# ar_env.net
KiCad netlist of a schematic drawn in EAGLE
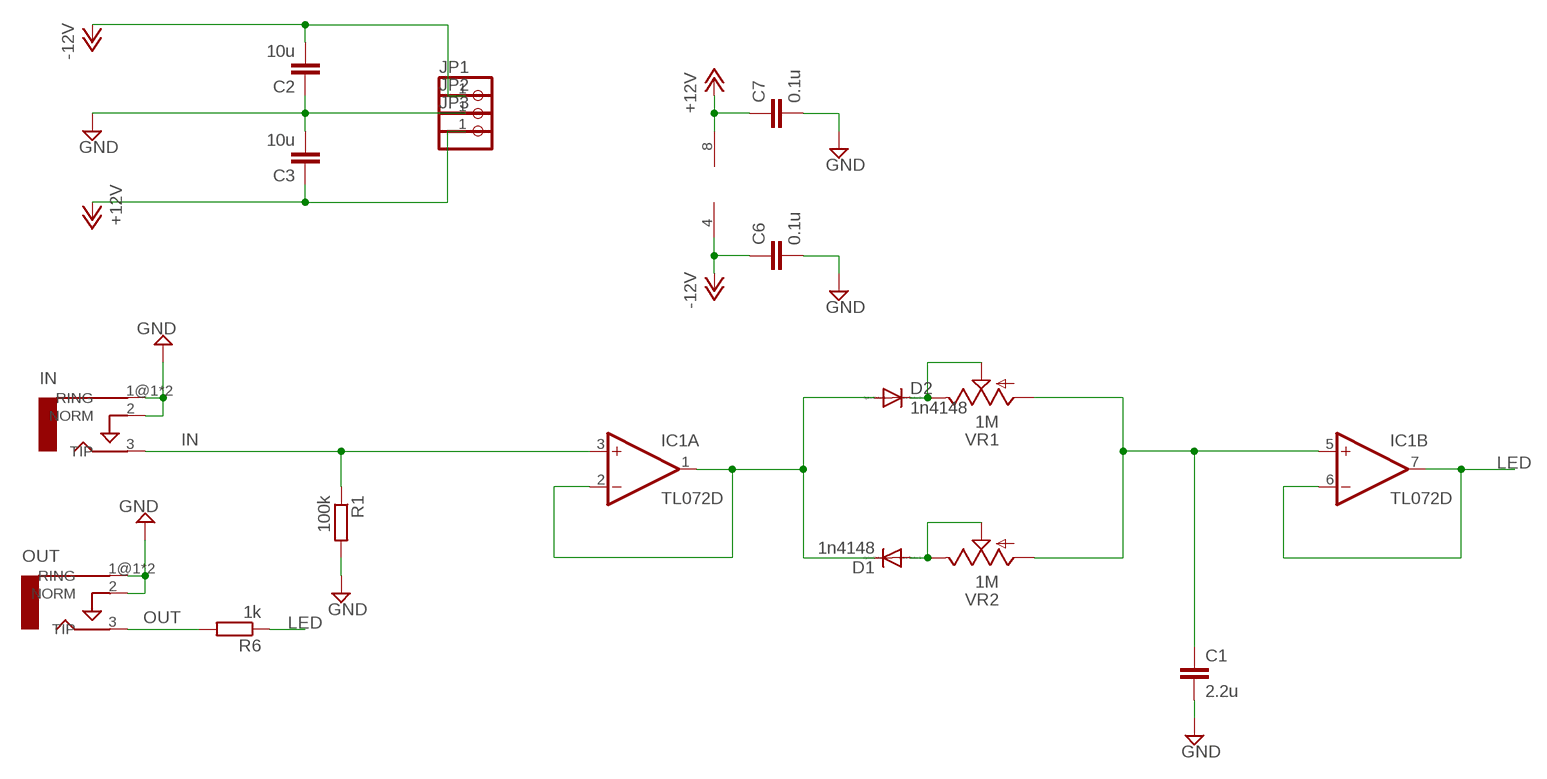
[diagram p0: schematic, sheet 1]

(export (version "E")
  (design (tool "Eeschema 10.0.6"))
  (components
    (comp (ref "C1")
      (value "2.2u")
      (footprint "eagle-import:C0805")
      (libsource (lib "eagle-import") (part "C-EUC0805"))
    )
    (comp (ref "C2")
      (value "10u")
      (footprint "eagle-import:C0805")
      (libsource (lib "eagle-import") (part "C-EUC0805"))
    )
    (comp (ref "C3")
      (value "10u")
      (footprint "eagle-import:C0805")
      (libsource (lib "eagle-import") (part "C-EUC0805"))
    )
    (comp (ref "C6")
      (value "0.1u")
      (footprint "eagle-import:C0805")
      (libsource (lib "eagle-import") (part "C-EUC0805"))
    )
    (comp (ref "C7")
      (value "0.1u")
      (footprint "eagle-import:C0805")
      (libsource (lib "eagle-import") (part "C-EUC0805"))
    )
    (comp (ref "D1")
      (value "1n4148")
      (footprint "eagle-import:SOD323-W")
      (libsource (lib "eagle-import") (part "DIODE-SOD323-W"))
    )
    (comp (ref "D2")
      (value "1n4148")
      (footprint "eagle-import:SOD323-W")
      (libsource (lib "eagle-import") (part "DIODE-SOD323-W"))
    )
    (comp (ref "IC1")
      (value "TL072D")
      (footprint "eagle-import:SO08")
      (libsource (lib "eagle-import") (part "TL072D"))
    )
    (comp (ref "IN")
      (value "AUDIO-JACKERTHENVAR")
      (footprint "eagle-import:ERTHENVAR-JACK")
      (libsource (lib "eagle-import") (part "AUDIO-JACKERTHENVAR"))
    )
    (comp (ref "JP1")
      (value "PINHD-1X1")
      (footprint "eagle-import:1X01")
      (libsource (lib "eagle-import") (part "PINHD-1X1"))
    )
    (comp (ref "JP2")
      (value "PINHD-1X1")
      (footprint "eagle-import:1X01")
      (libsource (lib "eagle-import") (part "PINHD-1X1"))
    )
    (comp (ref "JP3")
      (value "PINHD-1X1")
      (footprint "eagle-import:1X01")
      (libsource (lib "eagle-import") (part "PINHD-1X1"))
    )
    (comp (ref "OUT")
      (value "AUDIO-JACKERTHENVAR")
      (footprint "eagle-import:ERTHENVAR-JACK")
      (libsource (lib "eagle-import") (part "AUDIO-JACKERTHENVAR"))
    )
    (comp (ref "R1")
      (value "100k")
      (footprint "eagle-import:R0805")
      (libsource (lib "eagle-import") (part "R-EU_R0805"))
    )
    (comp (ref "R6")
      (value "1k")
      (footprint "eagle-import:R0805")
      (libsource (lib "eagle-import") (part "R-EU_R0805"))
    )
    (comp (ref "VR1")
      (value "1M")
      (footprint "eagle-import:9MM_SNAP-IN_POT")
      (libsource (lib "eagle-import") (part "9MM_SNAP-IN_POT_"))
    )
    (comp (ref "VR2")
      (value "1M")
      (footprint "eagle-import:9MM_SNAP-IN_POT")
      (libsource (lib "eagle-import") (part "9MM_SNAP-IN_POT_"))
    )
  )
  (nets
    (net (code "1") (name "+12V") (class "Default")
      (node (ref "C3") (pin "1") (pinfunction "1_1") (pintype "passive"))
      (node (ref "C7") (pin "1") (pinfunction "1_1") (pintype "passive"))
      (node (ref "IC1") (pin "8") (pinfunction "V+_8") (pintype "power_in"))
      (node (ref "JP3") (pin "1") (pinfunction "1_1") (pintype "passive"))
    )
    (net (code "2") (name "-12V") (class "Default")
      (node (ref "C2") (pin "2") (pinfunction "2_2") (pintype "passive"))
      (node (ref "C6") (pin "1") (pinfunction "1_1") (pintype "passive"))
      (node (ref "IC1") (pin "4") (pinfunction "V-_4") (pintype "power_in"))
      (node (ref "JP1") (pin "1") (pinfunction "1_1") (pintype "passive"))
    )
    (net (code "3") (name "/IN") (class "Default")
      (node (ref "IC1") (pin "3") (pinfunction "+IN_3") (pintype "input"))
      (node (ref "IN") (pin "3") (pinfunction "TIP_3") (pintype "bidirectional"))
      (node (ref "R1") (pin "1") (pinfunction "1_1") (pintype "passive"))
    )
    (net (code "4") (name "/LED") (class "Default")
      (node (ref "IC1") (pin "6") (pinfunction "-IN_6") (pintype "input"))
      (node (ref "IC1") (pin "7") (pinfunction "OUT_7") (pintype "output"))
      (node (ref "R6") (pin "1") (pinfunction "1_1") (pintype "passive"))
    )
    (net (code "5") (name "/OUT") (class "Default")
      (node (ref "OUT") (pin "3") (pinfunction "TIP_3") (pintype "bidirectional"))
      (node (ref "R6") (pin "2") (pinfunction "2_2") (pintype "passive"))
    )
    (net (code "6") (name "GND") (class "Default")
      (node (ref "C1") (pin "2") (pinfunction "2_2") (pintype "passive"))
      (node (ref "C2") (pin "1") (pinfunction "1_1") (pintype "passive"))
      (node (ref "C3") (pin "2") (pinfunction "2_2") (pintype "passive"))
      (node (ref "C6") (pin "2") (pinfunction "2_2") (pintype "passive"))
      (node (ref "C7") (pin "2") (pinfunction "2_2") (pintype "passive"))
      (node (ref "IN") (pin "1@1") (pinfunction "RING_1@1") (pintype "bidirectional"))
      (node (ref "IN") (pin "1@2") (pinfunction "RING_1@2") (pintype "bidirectional"))
      (node (ref "IN") (pin "2") (pinfunction "NORM_2") (pintype "bidirectional"))
      (node (ref "JP2") (pin "1") (pinfunction "1_1") (pintype "passive"))
      (node (ref "OUT") (pin "1@1") (pinfunction "RING_1@1") (pintype "bidirectional"))
      (node (ref "OUT") (pin "1@2") (pinfunction "RING_1@2") (pintype "bidirectional"))
      (node (ref "OUT") (pin "2") (pinfunction "NORM_2") (pintype "bidirectional"))
      (node (ref "R1") (pin "2") (pinfunction "2_2") (pintype "passive"))
    )
    (net (code "7") (name "Net-(IC1A--IN)") (class "Default")
      (node (ref "D1") (pin "C") (pinfunction "C_C") (pintype "passive"))
      (node (ref "D2") (pin "A") (pinfunction "A_A") (pintype "passive"))
      (node (ref "IC1") (pin "1") (pinfunction "OUT_1") (pintype "output"))
      (node (ref "IC1") (pin "2") (pinfunction "-IN_2") (pintype "input"))
    )
    (net (code "8") (name "Net-(IC1B-+IN)") (class "Default")
      (node (ref "C1") (pin "1") (pinfunction "1_1") (pintype "passive"))
      (node (ref "IC1") (pin "5") (pinfunction "+IN_5") (pintype "input"))
      (node (ref "VR1") (pin "1") (pinfunction "A_1") (pintype "passive"))
      (node (ref "VR2") (pin "1") (pinfunction "A_1") (pintype "passive"))
    )
    (net (code "9") (name "Net-(VR1-E)") (class "Default")
      (node (ref "D2") (pin "C") (pinfunction "C_C") (pintype "passive"))
      (node (ref "VR1") (pin "2") (pinfunction "S_2") (pintype "passive"))
      (node (ref "VR1") (pin "3") (pinfunction "E_3") (pintype "passive"))
    )
    (net (code "10") (name "Net-(VR2-E)") (class "Default")
      (node (ref "D1") (pin "A") (pinfunction "A_A") (pintype "passive"))
      (node (ref "VR2") (pin "2") (pinfunction "S_2") (pintype "passive"))
      (node (ref "VR2") (pin "3") (pinfunction "E_3") (pintype "passive"))
    )
  )
)
